# fonte.net
KiCad netlist of a schematic drawn in EAGLE
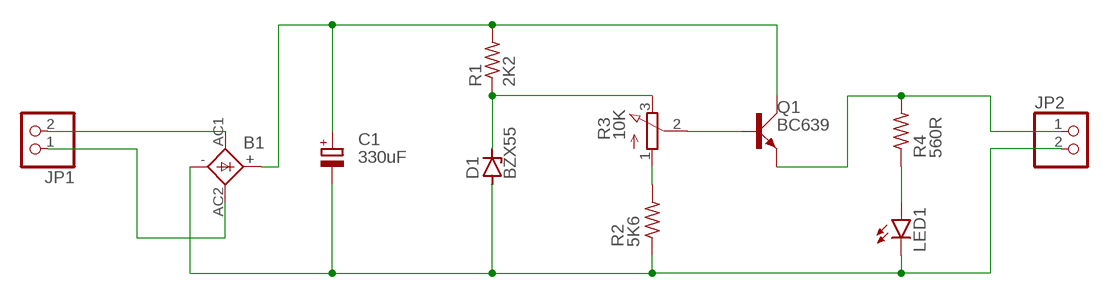
[diagram p0: schematic, sheet 1]

(export (version "E")
  (design (tool "Eeschema 10.0.6"))
  (components
    (comp (ref "B1")
      (value "1KAB")
      (footprint "eagle-import:1KAB")
      (libsource (lib "eagle-import") (part "1KAB"))
    )
    (comp (ref "C1")
      (value "330uF")
      (footprint "eagle-import:E3,5-10")
      (libsource (lib "eagle-import") (part "CPOL-EUE3.5-10"))
    )
    (comp (ref "D1")
      (value "BZX55")
      (footprint "eagle-import:DO35Z10")
      (libsource (lib "eagle-import") (part "BZX55"))
    )
    (comp (ref "JP1")
      (value "PINHD-1X2")
      (footprint "eagle-import:1X02")
      (libsource (lib "eagle-import") (part "PINHD-1X2"))
    )
    (comp (ref "JP2")
      (value "PINHD-1X2")
      (footprint "eagle-import:1X02")
      (libsource (lib "eagle-import") (part "PINHD-1X2"))
    )
    (comp (ref "LED1")
      (value "LED3MM")
      (footprint "eagle-import:LED3MM")
      (libsource (lib "eagle-import") (part "LED3MM"))
    )
    (comp (ref "Q1")
      (value "BC639")
      (footprint "eagle-import:SOT54D")
      (libsource (lib "eagle-import") (part "BC639"))
    )
    (comp (ref "R1")
      (value "2K2")
      (footprint "eagle-import:0309_12")
      (libsource (lib "eagle-import") (part "R-US_0309/12"))
    )
    (comp (ref "R2")
      (value "5K6")
      (footprint "eagle-import:0309_12")
      (libsource (lib "eagle-import") (part "R-US_0309/12"))
    )
    (comp (ref "R3")
      (value "10K")
      (footprint "eagle-import:3RP_1610N")
      (libsource (lib "eagle-import") (part "3RP/1610N"))
    )
    (comp (ref "R4")
      (value "560R")
      (footprint "eagle-import:0309_12")
      (libsource (lib "eagle-import") (part "R-US_0309/12"))
    )
  )
  (nets
    (net (code "1") (name "Net-(B1-Pad+)") (class "Default")
      (node (ref "B1") (pin "+") (pinfunction "+_+") (pintype "passive"))
      (node (ref "C1") (pin "+") (pinfunction "+_+") (pintype "passive"))
      (node (ref "Q1") (pin "C") (pinfunction "C_C") (pintype "passive"))
      (node (ref "R1") (pin "2") (pinfunction "2_2") (pintype "passive"))
    )
    (net (code "2") (name "Net-(B1-PadAC1)") (class "Default")
      (node (ref "B1") (pin "AC1") (pinfunction "AC1_AC1") (pintype "passive"))
      (node (ref "JP1") (pin "2") (pinfunction "2_2") (pintype "passive"))
    )
    (net (code "3") (name "Net-(B1-PadAC2)") (class "Default")
      (node (ref "B1") (pin "AC2") (pinfunction "AC2_AC2") (pintype "passive"))
      (node (ref "JP1") (pin "1") (pinfunction "1_1") (pintype "passive"))
    )
    (net (code "4") (name "Net-(JP2-Pad1)") (class "Default")
      (node (ref "JP2") (pin "1") (pinfunction "1_1") (pintype "passive"))
      (node (ref "Q1") (pin "E") (pinfunction "E_E") (pintype "passive"))
      (node (ref "R4") (pin "2") (pinfunction "2_2") (pintype "passive"))
    )
    (net (code "5") (name "Net-(LED1-C)") (class "Default")
      (node (ref "B1") (pin "-") (pinfunction "-_-") (pintype "passive"))
      (node (ref "C1") (pin "-") (pinfunction "-_-") (pintype "passive"))
      (node (ref "D1") (pin "A") (pinfunction "A_A") (pintype "passive"))
      (node (ref "JP2") (pin "2") (pinfunction "2_2") (pintype "passive"))
      (node (ref "LED1") (pin "K") (pinfunction "C_K") (pintype "passive"))
      (node (ref "R2") (pin "1") (pinfunction "1_1") (pintype "passive"))
    )
    (net (code "6") (name "Net-(LED1-PadA)") (class "Default")
      (node (ref "LED1") (pin "A") (pinfunction "A_A") (pintype "passive"))
      (node (ref "R4") (pin "1") (pinfunction "1_1") (pintype "passive"))
    )
    (net (code "7") (name "Net-(R3-A)") (class "Default")
      (node (ref "R2") (pin "2") (pinfunction "2_2") (pintype "passive"))
      (node (ref "R3") (pin "1") (pinfunction "A_1") (pintype "passive"))
    )
    (net (code "8") (name "Net-(R3-E)") (class "Default")
      (node (ref "D1") (pin "C") (pinfunction "C_C") (pintype "passive"))
      (node (ref "R1") (pin "1") (pinfunction "1_1") (pintype "passive"))
      (node (ref "R3") (pin "3") (pinfunction "E_3") (pintype "passive"))
    )
    (net (code "9") (name "Net-(R3-S)") (class "Default")
      (node (ref "Q1") (pin "B") (pinfunction "B_B") (pintype "passive"))
      (node (ref "R3") (pin "2") (pinfunction "S_2") (pintype "passive"))
    )
  )
)
